# adaptor.net
KiCad netlist of a schematic drawn in EAGLE
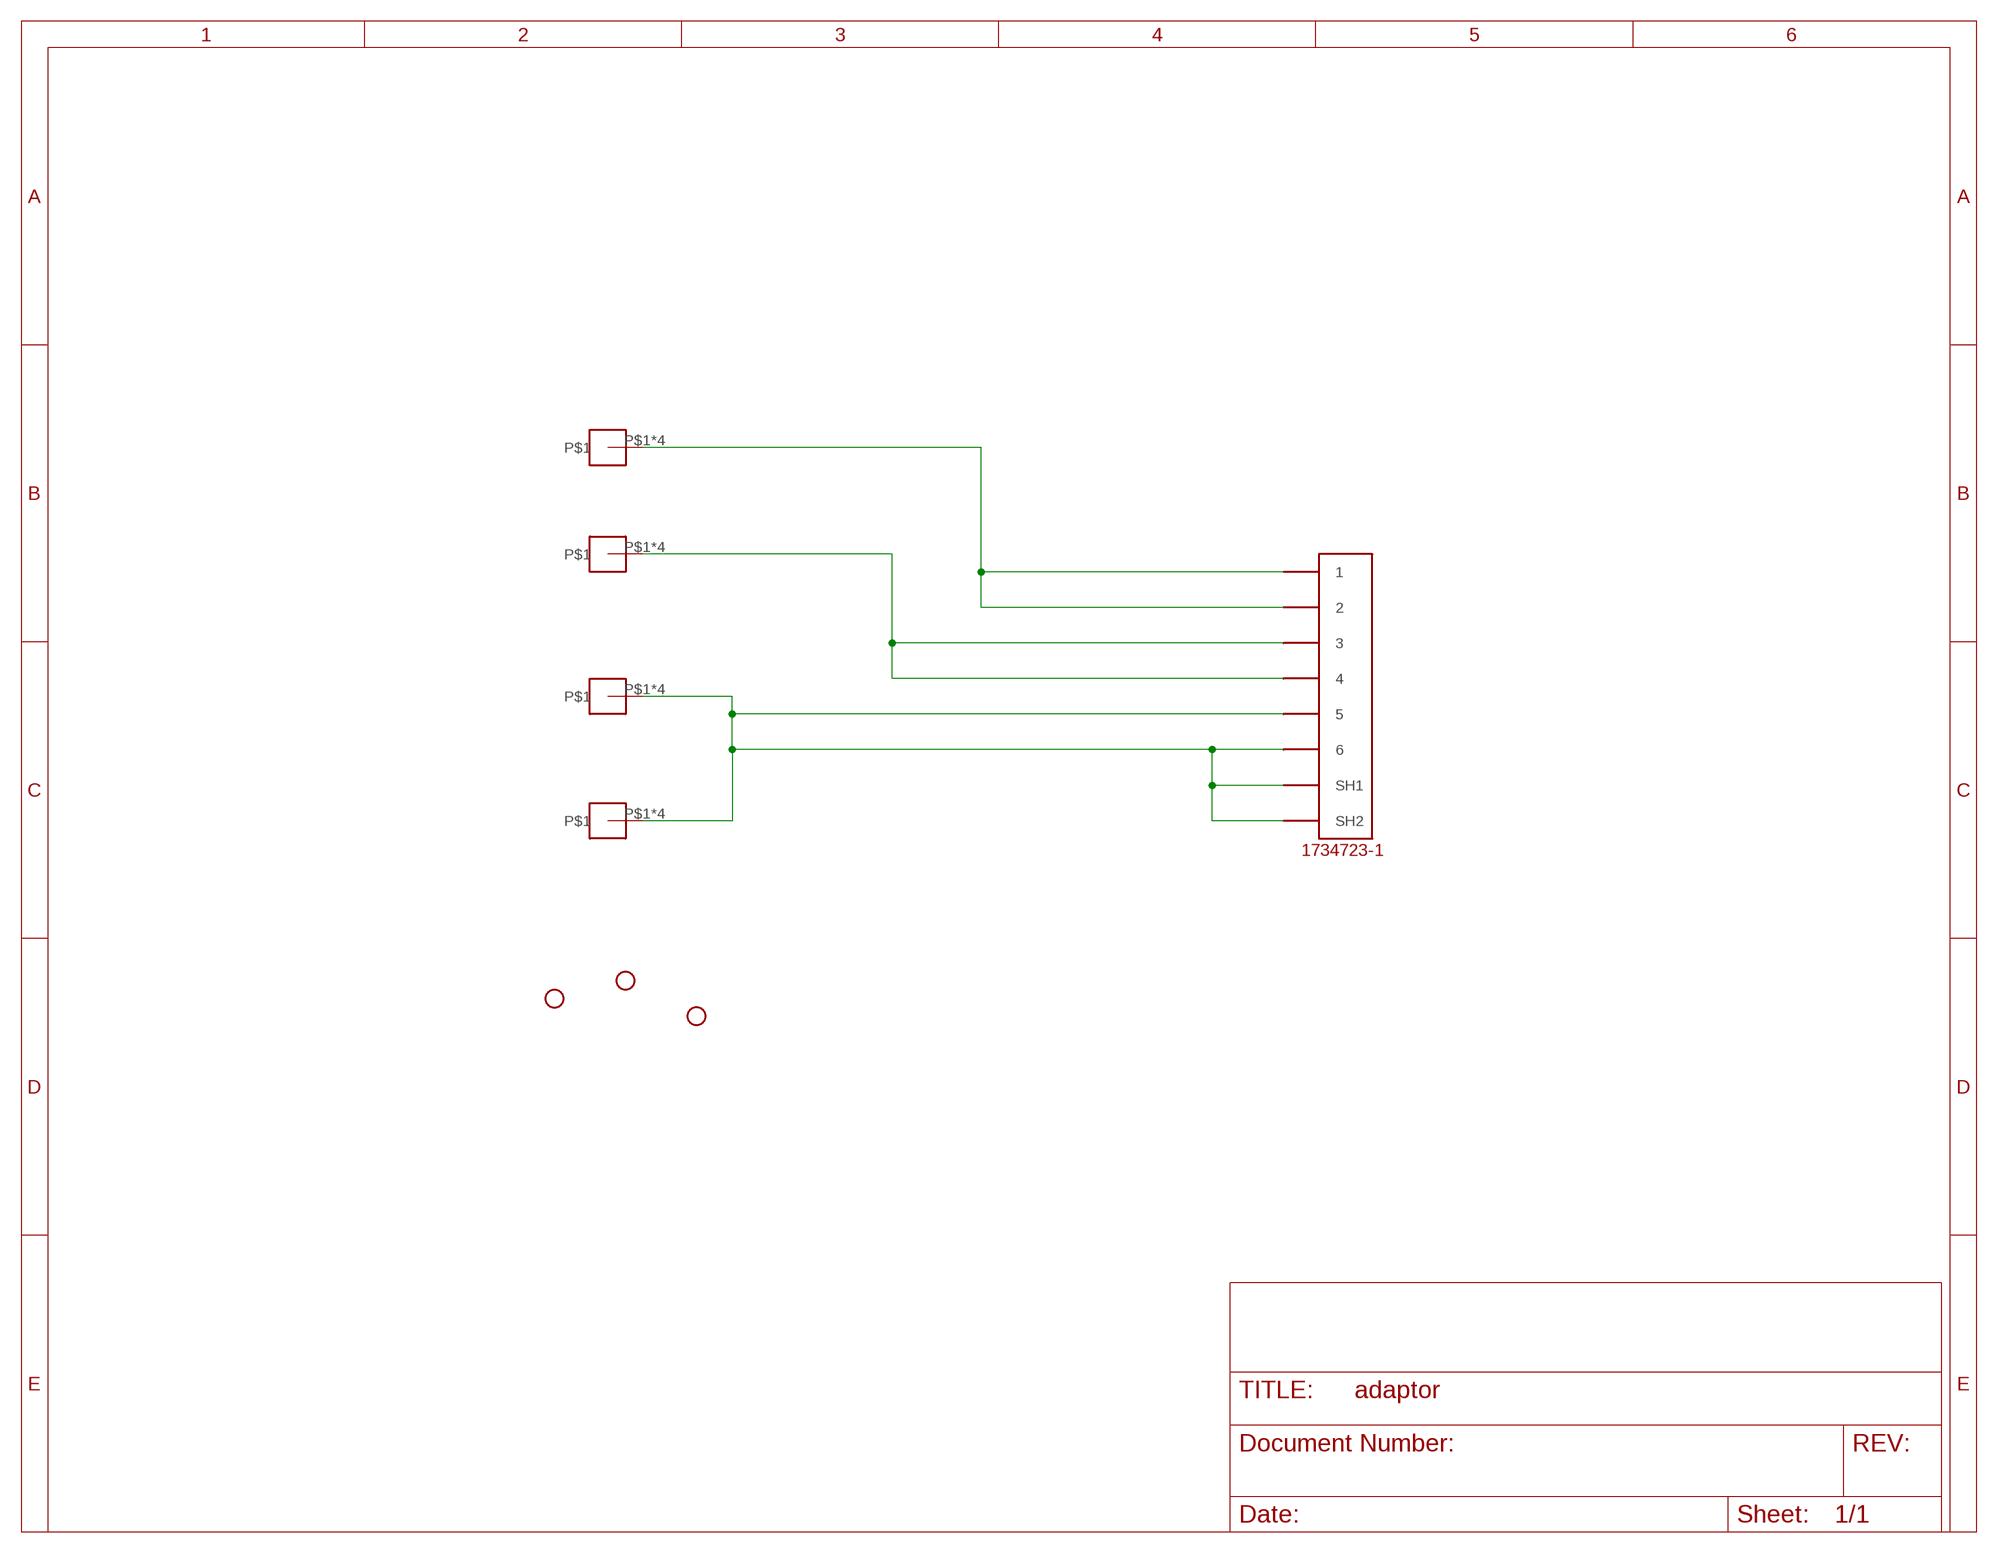
[diagram p0: schematic, sheet 1]

(export (version "E")
  (design (tool "Eeschema 10.0.6"))
  (components
    (comp (ref "H1")
      (value "STAND-OFF")
      (footprint "eagle-import:STAND-OFF")
      (libsource (lib "eagle-import") (part "STAND-OFF"))
    )
    (comp (ref "H2")
      (value "STAND-OFF")
      (footprint "eagle-import:STAND-OFF")
      (libsource (lib "eagle-import") (part "STAND-OFF"))
    )
    (comp (ref "H3")
      (value "STAND-OFF")
      (footprint "eagle-import:STAND-OFF")
      (libsource (lib "eagle-import") (part "STAND-OFF"))
    )
    (comp (ref "U$1")
      (value "SCREW-8191")
      (footprint "eagle-import:SCREW-8191")
      (libsource (lib "eagle-import") (part "SCREW-8191"))
    )
    (comp (ref "U$2")
      (value "SCREW-8191")
      (footprint "eagle-import:SCREW-8191")
      (libsource (lib "eagle-import") (part "SCREW-8191"))
    )
    (comp (ref "U$3")
      (value "5555140-6")
      (footprint "eagle-import:1734723-1_RJ11")
      (libsource (lib "eagle-import") (part "5555140-6"))
    )
    (comp (ref "U$4")
      (value "SCREW-8191")
      (footprint "eagle-import:SCREW-8191")
      (libsource (lib "eagle-import") (part "SCREW-8191"))
    )
    (comp (ref "U$6")
      (value "SCREW-8191")
      (footprint "eagle-import:SCREW-8191")
      (libsource (lib "eagle-import") (part "SCREW-8191"))
    )
  )
  (nets
    (net (code "1") (name "Net-(U$1-P$1-PadP$2)") (class "Default")
      (node (ref "U$1") (pin "P$1") (pinfunction "P$1_P$1") (pintype "bidirectional"))
      (node (ref "U$1") (pin "P$2") (pinfunction "P$1_P$2") (pintype "bidirectional"))
      (node (ref "U$1") (pin "P$3") (pinfunction "P$1_P$3") (pintype "bidirectional"))
      (node (ref "U$1") (pin "P$4") (pinfunction "P$1_P$4") (pintype "bidirectional"))
      (node (ref "U$3") (pin "3") (pinfunction "3_3") (pintype "bidirectional"))
      (node (ref "U$3") (pin "4") (pinfunction "4_4") (pintype "bidirectional"))
    )
    (net (code "2") (name "Net-(U$2-P$1-PadP$2)") (class "Default")
      (node (ref "U$2") (pin "P$1") (pinfunction "P$1_P$1") (pintype "bidirectional"))
      (node (ref "U$2") (pin "P$2") (pinfunction "P$1_P$2") (pintype "bidirectional"))
      (node (ref "U$2") (pin "P$3") (pinfunction "P$1_P$3") (pintype "bidirectional"))
      (node (ref "U$2") (pin "P$4") (pinfunction "P$1_P$4") (pintype "bidirectional"))
      (node (ref "U$3") (pin "5") (pinfunction "5_5") (pintype "bidirectional"))
      (node (ref "U$3") (pin "6") (pinfunction "6_6") (pintype "bidirectional"))
      (node (ref "U$3") (pin "SH1") (pinfunction "SH1_SH1") (pintype "bidirectional"))
      (node (ref "U$3") (pin "SH2") (pinfunction "SH2_SH2") (pintype "bidirectional"))
      (node (ref "U$4") (pin "P$1") (pinfunction "P$1_P$1") (pintype "bidirectional"))
      (node (ref "U$4") (pin "P$2") (pinfunction "P$1_P$2") (pintype "bidirectional"))
      (node (ref "U$4") (pin "P$3") (pinfunction "P$1_P$3") (pintype "bidirectional"))
      (node (ref "U$4") (pin "P$4") (pinfunction "P$1_P$4") (pintype "bidirectional"))
    )
    (net (code "3") (name "Net-(U$3-Pad1)") (class "Default")
      (node (ref "U$3") (pin "1") (pinfunction "1_1") (pintype "bidirectional"))
      (node (ref "U$3") (pin "2") (pinfunction "2_2") (pintype "bidirectional"))
      (node (ref "U$6") (pin "P$1") (pinfunction "P$1_P$1") (pintype "bidirectional"))
      (node (ref "U$6") (pin "P$2") (pinfunction "P$1_P$2") (pintype "bidirectional"))
      (node (ref "U$6") (pin "P$3") (pinfunction "P$1_P$3") (pintype "bidirectional"))
      (node (ref "U$6") (pin "P$4") (pinfunction "P$1_P$4") (pintype "bidirectional"))
    )
  )
)
